# ProDoc_ChisFlash-MBC5-v1_21_8M.net
KiCad netlist of a schematic drawn in EasyEDA Pro
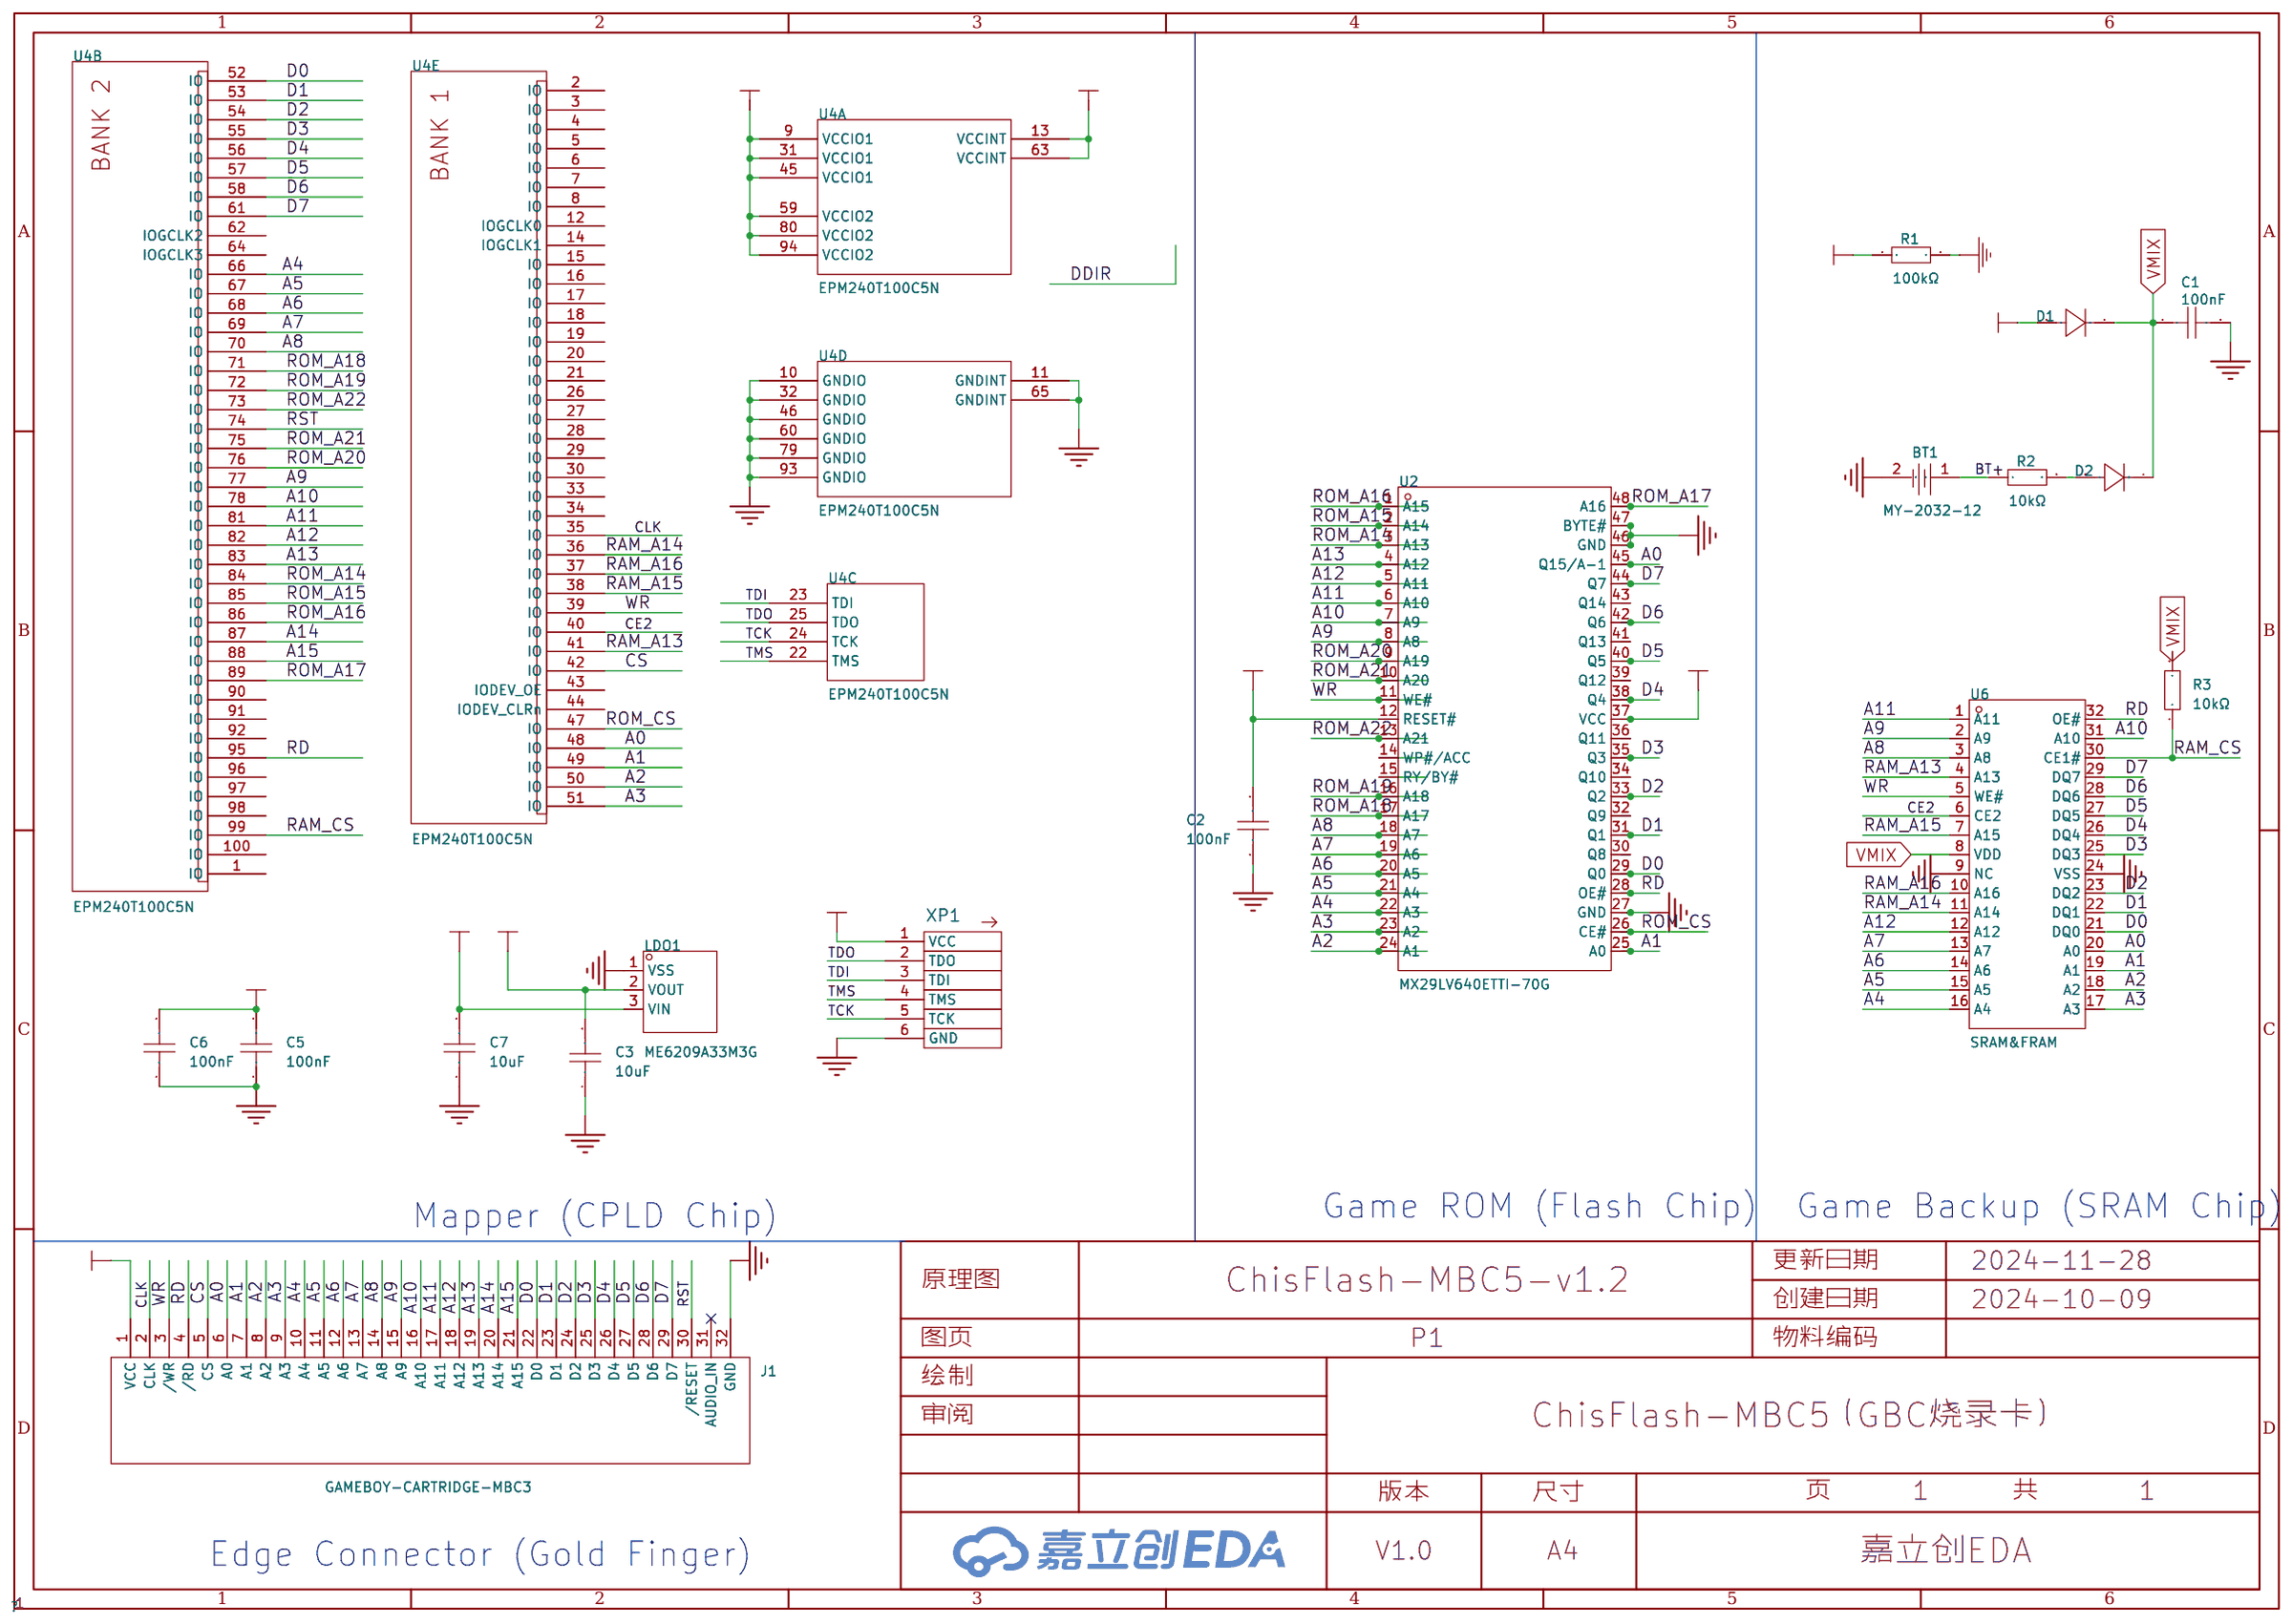
[diagram p0: schematic sheet]

(export (version "E")
  (design (tool "Eeschema 10.0.6"))
  (components
    (comp (ref "BT1")
      (value "MY-2032-12")
      (footprint "easyedapro:BAT-SMD_MY-2032-12")
      (fields (field (name "Manufacturer") "MYOUNG(美阳)"))
      (libsource (lib "easyedapro") (part "MY-2032-12"))
    )
    (comp (ref "C1")
      (value "100nF")
      (footprint "easyedapro:C0603")
      (description "容值:100nF;精度:±10%;额定电压:50V;材质(温度系数):X7R;")
      (fields
        (field (name "Manufacturer Part") "CGA0603X7R104K500JT")
        (field (name "Manufacturer") "HRE(芯声)")
      )
      (libsource (lib "easyedapro") (part "CGA0603X7R104K500JT"))
    )
    (comp (ref "C2")
      (value "100nF")
      (footprint "easyedapro:C0603")
      (description "容值:100nF;精度:±10%;额定电压:50V;材质(温度系数):X7R;")
      (fields
        (field (name "Manufacturer Part") "CGA0603X7R104K500JT")
        (field (name "Manufacturer") "HRE(芯声)")
      )
      (libsource (lib "easyedapro") (part "CGA0603X7R104K500JT"))
    )
    (comp (ref "C3")
      (value "10uF")
      (footprint "easyedapro:C0603")
      (description "容值:10uF;精度:±20%;额定电压:25V;材质(温度系数):X5R;")
      (fields
        (field (name "Manufacturer Part") "CL10A106MA8NRNC")
        (field (name "Manufacturer") "SAMSUNG(三星)")
      )
      (libsource (lib "easyedapro") (part "CL10A106MA8NRNC"))
    )
    (comp (ref "C5")
      (value "100nF")
      (footprint "easyedapro:C0603")
      (description "容值:100nF;精度:±10%;额定电压:50V;材质(温度系数):X7R;")
      (fields
        (field (name "Manufacturer Part") "CGA0603X7R104K500JT")
        (field (name "Manufacturer") "HRE(芯声)")
      )
      (libsource (lib "easyedapro") (part "CGA0603X7R104K500JT"))
    )
    (comp (ref "C6")
      (value "100nF")
      (footprint "easyedapro:C0603")
      (description "容值:100nF;精度:±10%;额定电压:50V;材质(温度系数):X7R;")
      (fields
        (field (name "Manufacturer Part") "CGA0603X7R104K500JT")
        (field (name "Manufacturer") "HRE(芯声)")
      )
      (libsource (lib "easyedapro") (part "CGA0603X7R104K500JT"))
    )
    (comp (ref "C7")
      (value "10uF")
      (footprint "easyedapro:C0603")
      (description "容值:10uF;精度:±20%;额定电压:25V;材质(温度系数):X5R;")
      (fields
        (field (name "Manufacturer Part") "CL10A106MA8NRNC")
        (field (name "Manufacturer") "SAMSUNG(三星)")
      )
      (libsource (lib "easyedapro") (part "CL10A106MA8NRNC"))
    )
    (comp (ref "D1")
      (value "1N4148WS")
      (footprint "easyedapro:SOD-323_L1.8-W1.3-LS2.5-RD")
      (description "二极管配置:独立式;正向压降(Vf):1.25V@150mA;直流反向耐压(Vr):100V;平均整流电流(Io):300mA;功率:400mW;反向恢复时间(trr):8ns;")
      (fields (field (name "Manufacturer") "JSMSEMI(杰盛微)"))
      (libsource (lib "easyedapro") (part "1N4148WS_C917117"))
    )
    (comp (ref "D2")
      (value "1N4148WS")
      (footprint "easyedapro:SOD-323_L1.8-W1.3-LS2.5-RD")
      (description "二极管配置:独立式;正向压降(Vf):1.25V@150mA;直流反向耐压(Vr):100V;平均整流电流(Io):300mA;功率:400mW;反向恢复时间(trr):8ns;")
      (fields (field (name "Manufacturer") "JSMSEMI(杰盛微)"))
      (libsource (lib "easyedapro") (part "1N4148WS_C917117"))
    )
    (comp (ref "J1")
      (value "GAMEBOY-CARTRIDGE-MBC3")
      (footprint "easyedapro:GAMEBOY_CARTRIDGE_PIN")
      (libsource (lib "easyedapro") (part "GAMEBOY-CARTRIDGE-MBC3"))
    )
    (comp (ref "LDO1")
      (value "ME6209A33M3G")
      (footprint "easyedapro:SOT-23-3_L2.9-W1.6-P1.90-LS2.8-BR")
      (description "输出类型:固定;最大输入电压:18V;输出电压:3.3V;最大输出电流:250mA;电源纹波抑制比(PSRR):-;输出极性:正极;")
      (fields (field (name "Manufacturer") "MICRONE(南京微盟)"))
      (libsource (lib "easyedapro") (part "ME6209A33M3G"))
    )
    (comp (ref "R1")
      (value "100kΩ")
      (footprint "easyedapro:R0603")
      (description "电阻类型:厚膜电阻;阻值:100kΩ;精度:±1%;功率:100mW;最大工作电压:75V;温度系数:±100ppm/°C;")
      (fields
        (field (name "Manufacturer Part") "0603WAF1003T5E")
        (field (name "Manufacturer") "UNI-ROYAL(厚声)")
      )
      (libsource (lib "easyedapro") (part "0603WAF1003T5E"))
    )
    (comp (ref "R2")
      (value "10kΩ")
      (footprint "easyedapro:R0603")
      (description "电阻类型:厚膜电阻;阻值:10kΩ;精度:±1%;功率:100mW;温度系数:±100ppm/°C;最大工作电压:75V;工作温度范围:-55°C~+155°C;")
      (fields
        (field (name "Manufacturer Part") "0603WAF1002T5E")
        (field (name "Manufacturer") "UNI-ROYAL(厚声)")
      )
      (libsource (lib "easyedapro") (part "0603WAF1002T5E"))
    )
    (comp (ref "R3")
      (value "10kΩ")
      (footprint "easyedapro:R0603")
      (description "电阻类型:厚膜电阻;阻值:10kΩ;精度:±1%;功率:100mW;温度系数:±100ppm/°C;最大工作电压:75V;工作温度范围:-55°C~+155°C;")
      (fields
        (field (name "Manufacturer Part") "0603WAF1002T5E")
        (field (name "Manufacturer") "UNI-ROYAL(厚声)")
      )
      (libsource (lib "easyedapro") (part "0603WAF1002T5E"))
    )
    (comp (ref "U2")
      (value "MX29LV640ETTI-70G")
      (footprint "easyedapro:TSOP-48_L12.0-W18.4-P0.50-LS20.0-BL")
      (fields (field (name "Manufacturer") "MXIC(旺宏电子)"))
      (libsource (lib "easyedapro") (part "MX29LV640ETTI-70G"))
    )
    (comp (ref "U4")
      (value "EPM240T100C5N")
      (footprint "easyedapro:TQFP-100_L14.0-W14.0-P0.50-LS16.0-BL")
      (description "类型:其它PLD;逻辑门数量:-;逻辑单元数:-;逻辑阵列块数:240;")
      (fields (field (name "Manufacturer") "Intel/Altera"))
      (libsource (lib "easyedapro") (part "EPM240T100C5N"))
    )
    (comp (ref "U6")
      (value "SRAM&FRAM")
      (footprint "easyedapro:TSSOP-TSOP二合一")
      (libsource (lib "easyedapro") (part "SRAM&FRAM"))
    )
    (comp (ref "XP1")
      (value "JTAG")
      (footprint "easyedapro:HDR-TH_6P-P1.27-V-M-1")
      (libsource (lib "easyedapro") (part "jtag"))
    )
  )
  (nets
    (net (code "1") (name "+3V3") (class "Default")
      (node (ref "C2") (pin "2") (pinfunction "2_2") (pintype "unspecified"))
      (node (ref "C3") (pin "2") (pinfunction "2_2") (pintype "unspecified"))
      (node (ref "C5") (pin "2") (pinfunction "2_2") (pintype "unspecified"))
      (node (ref "C6") (pin "2") (pinfunction "2_2") (pintype "unspecified"))
      (node (ref "D1") (pin "2") (pinfunction "A_2") (pintype "unspecified"))
      (node (ref "LDO1") (pin "2") (pinfunction "VOUT_2") (pintype "unspecified"))
      (node (ref "R1") (pin "1") (pinfunction "1_1") (pintype "input"))
      (node (ref "U2") (pin "12") (pinfunction "RESET#_12") (pintype "unspecified"))
      (node (ref "U2") (pin "37") (pinfunction "VCC_37") (pintype "unspecified"))
      (node (ref "U4") (pin "13") (pinfunction "VCCINT_13") (pintype "unspecified"))
      (node (ref "U4") (pin "31") (pinfunction "VCCIO1_31") (pintype "unspecified"))
      (node (ref "U4") (pin "45") (pinfunction "VCCIO1_45") (pintype "unspecified"))
      (node (ref "U4") (pin "59") (pinfunction "VCCIO2_59") (pintype "unspecified"))
      (node (ref "U4") (pin "63") (pinfunction "VCCINT_63") (pintype "unspecified"))
      (node (ref "U4") (pin "80") (pinfunction "VCCIO2_80") (pintype "unspecified"))
      (node (ref "U4") (pin "9") (pinfunction "VCCIO1_9") (pintype "unspecified"))
      (node (ref "U4") (pin "94") (pinfunction "VCCIO2_94") (pintype "unspecified"))
      (node (ref "XP1") (pin "1") (pinfunction "VCC_1") (pintype "output"))
    )
    (net (code "2") (name "+5V") (class "Default")
      (node (ref "C7") (pin "2") (pinfunction "2_2") (pintype "unspecified"))
      (node (ref "J1") (pin "1") (pinfunction "VCC_1") (pintype "unspecified"))
      (node (ref "LDO1") (pin "3") (pinfunction "VIN_3") (pintype "unspecified"))
    )
    (net (code "3") (name "/A0") (class "Default")
      (node (ref "J1") (pin "6") (pinfunction "A0_6") (pintype "unspecified"))
      (node (ref "U2") (pin "45") (pinfunction "Q15/A-1_45") (pintype "unspecified"))
      (node (ref "U4") (pin "48") (pinfunction "IO_48") (pintype "bidirectional"))
      (node (ref "U6") (pin "20") (pinfunction "A0_20") (pintype "unspecified"))
    )
    (net (code "4") (name "/A1") (class "Default")
      (node (ref "J1") (pin "7") (pinfunction "A1_7") (pintype "unspecified"))
      (node (ref "U2") (pin "25") (pinfunction "A0_25") (pintype "unspecified"))
      (node (ref "U4") (pin "49") (pinfunction "IO_49") (pintype "bidirectional"))
      (node (ref "U6") (pin "19") (pinfunction "A1_19") (pintype "unspecified"))
    )
    (net (code "5") (name "/A2") (class "Default")
      (node (ref "J1") (pin "8") (pinfunction "A2_8") (pintype "unspecified"))
      (node (ref "U2") (pin "24") (pinfunction "A1_24") (pintype "unspecified"))
      (node (ref "U4") (pin "50") (pinfunction "IO_50") (pintype "bidirectional"))
      (node (ref "U6") (pin "18") (pinfunction "A2_18") (pintype "unspecified"))
    )
    (net (code "6") (name "/A3") (class "Default")
      (node (ref "J1") (pin "9") (pinfunction "A3_9") (pintype "unspecified"))
      (node (ref "U2") (pin "23") (pinfunction "A2_23") (pintype "unspecified"))
      (node (ref "U4") (pin "51") (pinfunction "IO_51") (pintype "bidirectional"))
      (node (ref "U6") (pin "17") (pinfunction "A3_17") (pintype "unspecified"))
    )
    (net (code "7") (name "/A4") (class "Default")
      (node (ref "J1") (pin "10") (pinfunction "A4_10") (pintype "unspecified"))
      (node (ref "U2") (pin "22") (pinfunction "A3_22") (pintype "unspecified"))
      (node (ref "U4") (pin "66") (pinfunction "IO_66") (pintype "bidirectional"))
      (node (ref "U6") (pin "16") (pinfunction "A4_16") (pintype "unspecified"))
    )
    (net (code "8") (name "/A5") (class "Default")
      (node (ref "J1") (pin "11") (pinfunction "A5_11") (pintype "unspecified"))
      (node (ref "U2") (pin "21") (pinfunction "A4_21") (pintype "unspecified"))
      (node (ref "U4") (pin "67") (pinfunction "IO_67") (pintype "bidirectional"))
      (node (ref "U6") (pin "15") (pinfunction "A5_15") (pintype "unspecified"))
    )
    (net (code "9") (name "/A6") (class "Default")
      (node (ref "J1") (pin "12") (pinfunction "A6_12") (pintype "unspecified"))
      (node (ref "U2") (pin "20") (pinfunction "A5_20") (pintype "unspecified"))
      (node (ref "U4") (pin "68") (pinfunction "IO_68") (pintype "bidirectional"))
      (node (ref "U6") (pin "14") (pinfunction "A6_14") (pintype "unspecified"))
    )
    (net (code "10") (name "/A7") (class "Default")
      (node (ref "J1") (pin "13") (pinfunction "A7_13") (pintype "unspecified"))
      (node (ref "U2") (pin "19") (pinfunction "A6_19") (pintype "unspecified"))
      (node (ref "U4") (pin "69") (pinfunction "IO_69") (pintype "bidirectional"))
      (node (ref "U6") (pin "13") (pinfunction "A7_13") (pintype "unspecified"))
    )
    (net (code "11") (name "/A8") (class "Default")
      (node (ref "J1") (pin "14") (pinfunction "A8_14") (pintype "unspecified"))
      (node (ref "U2") (pin "18") (pinfunction "A7_18") (pintype "unspecified"))
      (node (ref "U4") (pin "70") (pinfunction "IO_70") (pintype "bidirectional"))
      (node (ref "U6") (pin "3") (pinfunction "A8_3") (pintype "unspecified"))
    )
    (net (code "12") (name "/A9") (class "Default")
      (node (ref "J1") (pin "15") (pinfunction "A9_15") (pintype "unspecified"))
      (node (ref "U2") (pin "8") (pinfunction "A8_8") (pintype "unspecified"))
      (node (ref "U4") (pin "77") (pinfunction "IO_77") (pintype "bidirectional"))
      (node (ref "U6") (pin "2") (pinfunction "A9_2") (pintype "unspecified"))
    )
    (net (code "13") (name "/A10") (class "Default")
      (node (ref "J1") (pin "16") (pinfunction "A10_16") (pintype "unspecified"))
      (node (ref "U2") (pin "7") (pinfunction "A9_7") (pintype "unspecified"))
      (node (ref "U4") (pin "78") (pinfunction "IO_78") (pintype "bidirectional"))
      (node (ref "U6") (pin "31") (pinfunction "A10_31") (pintype "unspecified"))
    )
    (net (code "14") (name "/A11") (class "Default")
      (node (ref "J1") (pin "17") (pinfunction "A11_17") (pintype "unspecified"))
      (node (ref "U2") (pin "6") (pinfunction "A10_6") (pintype "unspecified"))
      (node (ref "U4") (pin "81") (pinfunction "IO_81") (pintype "bidirectional"))
      (node (ref "U6") (pin "1") (pinfunction "A11_1") (pintype "unspecified"))
    )
    (net (code "15") (name "/A12") (class "Default")
      (node (ref "J1") (pin "18") (pinfunction "A12_18") (pintype "unspecified"))
      (node (ref "U2") (pin "5") (pinfunction "A11_5") (pintype "unspecified"))
      (node (ref "U4") (pin "82") (pinfunction "IO_82") (pintype "bidirectional"))
      (node (ref "U6") (pin "12") (pinfunction "A12_12") (pintype "unspecified"))
    )
    (net (code "16") (name "/A13") (class "Default")
      (node (ref "J1") (pin "19") (pinfunction "A13_19") (pintype "unspecified"))
      (node (ref "U2") (pin "4") (pinfunction "A12_4") (pintype "unspecified"))
      (node (ref "U4") (pin "83") (pinfunction "IO_83") (pintype "bidirectional"))
    )
    (net (code "17") (name "/A14") (class "Default")
      (node (ref "J1") (pin "20") (pinfunction "A14_20") (pintype "unspecified"))
      (node (ref "U4") (pin "87") (pinfunction "IO_87") (pintype "bidirectional"))
    )
    (net (code "18") (name "/A15") (class "Default")
      (node (ref "J1") (pin "21") (pinfunction "A15_21") (pintype "unspecified"))
      (node (ref "U4") (pin "88") (pinfunction "IO_88") (pintype "bidirectional"))
    )
    (net (code "19") (name "/BT+") (class "Default")
      (node (ref "BT1") (pin "1") (pinfunction "1_1") (pintype "input"))
      (node (ref "R2") (pin "1") (pinfunction "1_1") (pintype "input"))
    )
    (net (code "20") (name "/CE2") (class "Default")
      (node (ref "U4") (pin "40") (pinfunction "IO_40") (pintype "bidirectional"))
      (node (ref "U6") (pin "6") (pinfunction "CE2_6") (pintype "unspecified"))
    )
    (net (code "21") (name "/CLK") (class "Default")
      (node (ref "J1") (pin "2") (pinfunction "CLK_2") (pintype "unspecified"))
      (node (ref "U4") (pin "35") (pinfunction "IO_35") (pintype "bidirectional"))
    )
    (net (code "22") (name "/CS") (class "Default")
      (node (ref "J1") (pin "5") (pinfunction "CS_5") (pintype "unspecified"))
      (node (ref "U4") (pin "42") (pinfunction "IO_42") (pintype "bidirectional"))
    )
    (net (code "23") (name "/D0") (class "Default")
      (node (ref "J1") (pin "22") (pinfunction "D0_22") (pintype "unspecified"))
      (node (ref "U2") (pin "29") (pinfunction "Q0_29") (pintype "unspecified"))
      (node (ref "U4") (pin "52") (pinfunction "IO_52") (pintype "bidirectional"))
      (node (ref "U6") (pin "21") (pinfunction "DQ0_21") (pintype "unspecified"))
    )
    (net (code "24") (name "/D1") (class "Default")
      (node (ref "J1") (pin "23") (pinfunction "D1_23") (pintype "unspecified"))
      (node (ref "U2") (pin "31") (pinfunction "Q1_31") (pintype "unspecified"))
      (node (ref "U4") (pin "53") (pinfunction "IO_53") (pintype "bidirectional"))
      (node (ref "U6") (pin "22") (pinfunction "DQ1_22") (pintype "unspecified"))
    )
    (net (code "25") (name "/D2") (class "Default")
      (node (ref "J1") (pin "24") (pinfunction "D2_24") (pintype "unspecified"))
      (node (ref "U2") (pin "33") (pinfunction "Q2_33") (pintype "unspecified"))
      (node (ref "U4") (pin "54") (pinfunction "IO_54") (pintype "bidirectional"))
      (node (ref "U6") (pin "23") (pinfunction "DQ2_23") (pintype "unspecified"))
    )
    (net (code "26") (name "/D3") (class "Default")
      (node (ref "J1") (pin "25") (pinfunction "D3_25") (pintype "unspecified"))
      (node (ref "U2") (pin "35") (pinfunction "Q3_35") (pintype "unspecified"))
      (node (ref "U4") (pin "55") (pinfunction "IO_55") (pintype "bidirectional"))
      (node (ref "U6") (pin "25") (pinfunction "DQ3_25") (pintype "unspecified"))
    )
    (net (code "27") (name "/D4") (class "Default")
      (node (ref "J1") (pin "26") (pinfunction "D4_26") (pintype "unspecified"))
      (node (ref "U2") (pin "38") (pinfunction "Q4_38") (pintype "unspecified"))
      (node (ref "U4") (pin "56") (pinfunction "IO_56") (pintype "bidirectional"))
      (node (ref "U6") (pin "26") (pinfunction "DQ4_26") (pintype "unspecified"))
    )
    (net (code "28") (name "/D5") (class "Default")
      (node (ref "J1") (pin "27") (pinfunction "D5_27") (pintype "unspecified"))
      (node (ref "U2") (pin "40") (pinfunction "Q5_40") (pintype "unspecified"))
      (node (ref "U4") (pin "57") (pinfunction "IO_57") (pintype "bidirectional"))
      (node (ref "U6") (pin "27") (pinfunction "DQ5_27") (pintype "unspecified"))
    )
    (net (code "29") (name "/D6") (class "Default")
      (node (ref "J1") (pin "28") (pinfunction "D6_28") (pintype "unspecified"))
      (node (ref "U2") (pin "42") (pinfunction "Q6_42") (pintype "unspecified"))
      (node (ref "U4") (pin "58") (pinfunction "IO_58") (pintype "bidirectional"))
      (node (ref "U6") (pin "28") (pinfunction "DQ6_28") (pintype "unspecified"))
    )
    (net (code "30") (name "/D7") (class "Default")
      (node (ref "J1") (pin "29") (pinfunction "D7_29") (pintype "unspecified"))
      (node (ref "U2") (pin "44") (pinfunction "Q7_44") (pintype "unspecified"))
      (node (ref "U4") (pin "61") (pinfunction "IO_61") (pintype "bidirectional"))
      (node (ref "U6") (pin "29") (pinfunction "DQ7_29") (pintype "unspecified"))
    )
    (net (code "32") (name "/RAM_A13") (class "Default")
      (node (ref "U4") (pin "41") (pinfunction "IO_41") (pintype "bidirectional"))
      (node (ref "U6") (pin "4") (pinfunction "A13_4") (pintype "unspecified"))
    )
    (net (code "33") (name "/RAM_A14") (class "Default")
      (node (ref "U4") (pin "36") (pinfunction "IO_36") (pintype "bidirectional"))
      (node (ref "U6") (pin "11") (pinfunction "A14_11") (pintype "unspecified"))
    )
    (net (code "34") (name "/RAM_A15") (class "Default")
      (node (ref "U4") (pin "38") (pinfunction "IO_38") (pintype "bidirectional"))
      (node (ref "U6") (pin "7") (pinfunction "A15_7") (pintype "unspecified"))
    )
    (net (code "35") (name "/RAM_A16") (class "Default")
      (node (ref "U4") (pin "37") (pinfunction "IO_37") (pintype "bidirectional"))
      (node (ref "U6") (pin "10") (pinfunction "A16_10") (pintype "unspecified"))
    )
    (net (code "36") (name "/RAM_CS") (class "Default")
      (node (ref "R3") (pin "1") (pinfunction "1_1") (pintype "input"))
      (node (ref "U4") (pin "99") (pinfunction "IO_99") (pintype "bidirectional"))
      (node (ref "U6") (pin "30") (pinfunction "CE1#_30") (pintype "unspecified"))
    )
    (net (code "37") (name "/RD") (class "Default")
      (node (ref "J1") (pin "4") (pinfunction "/RD_4") (pintype "unspecified"))
      (node (ref "U2") (pin "28") (pinfunction "OE#_28") (pintype "unspecified"))
      (node (ref "U4") (pin "95") (pinfunction "IO_95") (pintype "bidirectional"))
      (node (ref "U6") (pin "32") (pinfunction "OE#_32") (pintype "unspecified"))
    )
    (net (code "38") (name "/ROM_A14") (class "Default")
      (node (ref "U2") (pin "3") (pinfunction "A13_3") (pintype "unspecified"))
      (node (ref "U4") (pin "84") (pinfunction "IO_84") (pintype "bidirectional"))
    )
    (net (code "39") (name "/ROM_A15") (class "Default")
      (node (ref "U2") (pin "2") (pinfunction "A14_2") (pintype "unspecified"))
      (node (ref "U4") (pin "85") (pinfunction "IO_85") (pintype "bidirectional"))
    )
    (net (code "40") (name "/ROM_A16") (class "Default")
      (node (ref "U2") (pin "1") (pinfunction "A15_1") (pintype "unspecified"))
      (node (ref "U4") (pin "86") (pinfunction "IO_86") (pintype "bidirectional"))
    )
    (net (code "41") (name "/ROM_A17") (class "Default")
      (node (ref "U2") (pin "48") (pinfunction "A16_48") (pintype "unspecified"))
      (node (ref "U4") (pin "89") (pinfunction "IO_89") (pintype "bidirectional"))
    )
    (net (code "42") (name "/ROM_A18") (class "Default")
      (node (ref "U2") (pin "17") (pinfunction "A17_17") (pintype "unspecified"))
      (node (ref "U4") (pin "71") (pinfunction "IO_71") (pintype "bidirectional"))
    )
    (net (code "43") (name "/ROM_A19") (class "Default")
      (node (ref "U2") (pin "16") (pinfunction "A18_16") (pintype "unspecified"))
      (node (ref "U4") (pin "72") (pinfunction "IO_72") (pintype "bidirectional"))
    )
    (net (code "44") (name "/ROM_A20") (class "Default")
      (node (ref "U2") (pin "9") (pinfunction "A19_9") (pintype "unspecified"))
      (node (ref "U4") (pin "76") (pinfunction "IO_76") (pintype "bidirectional"))
    )
    (net (code "45") (name "/ROM_A21") (class "Default")
      (node (ref "U2") (pin "10") (pinfunction "A20_10") (pintype "unspecified"))
      (node (ref "U4") (pin "75") (pinfunction "IO_75") (pintype "bidirectional"))
    )
    (net (code "46") (name "/ROM_A22") (class "Default")
      (node (ref "U2") (pin "13") (pinfunction "A21_13") (pintype "unspecified"))
      (node (ref "U4") (pin "73") (pinfunction "IO_73") (pintype "bidirectional"))
    )
    (net (code "47") (name "/ROM_CS") (class "Default")
      (node (ref "U2") (pin "26") (pinfunction "CE#_26") (pintype "unspecified"))
      (node (ref "U4") (pin "47") (pinfunction "IO_47") (pintype "bidirectional"))
    )
    (net (code "48") (name "/RST") (class "Default")
      (node (ref "J1") (pin "30") (pinfunction "/RESET_30") (pintype "unspecified"))
      (node (ref "U4") (pin "74") (pinfunction "IO_74") (pintype "bidirectional"))
    )
    (net (code "49") (name "/TCK") (class "Default")
      (node (ref "U4") (pin "24") (pinfunction "TCK_24") (pintype "unspecified"))
      (node (ref "XP1") (pin "5") (pinfunction "TCK_5") (pintype "input"))
    )
    (net (code "50") (name "/TDI") (class "Default")
      (node (ref "U4") (pin "23") (pinfunction "TDI_23") (pintype "unspecified"))
      (node (ref "XP1") (pin "3") (pinfunction "TDI_3") (pintype "output"))
    )
    (net (code "51") (name "/TDO") (class "Default")
      (node (ref "U4") (pin "25") (pinfunction "TDO_25") (pintype "output"))
      (node (ref "XP1") (pin "2") (pinfunction "TDO_2") (pintype "output"))
    )
    (net (code "52") (name "/TMS") (class "Default")
      (node (ref "U4") (pin "22") (pinfunction "TMS_22") (pintype "unspecified"))
      (node (ref "XP1") (pin "4") (pinfunction "TMS_4") (pintype "output"))
    )
    (net (code "53") (name "/WR") (class "Default")
      (node (ref "J1") (pin "3") (pinfunction "/WR_3") (pintype "unspecified"))
      (node (ref "U2") (pin "11") (pinfunction "WE#_11") (pintype "unspecified"))
      (node (ref "U4") (pin "39") (pinfunction "IO_39") (pintype "bidirectional"))
      (node (ref "U6") (pin "5") (pinfunction "WE#_5") (pintype "unspecified"))
    )
    (net (code "54") (name "GND") (class "Default")
      (node (ref "BT1") (pin "2") (pinfunction "2_2") (pintype "input"))
      (node (ref "C1") (pin "2") (pinfunction "2_2") (pintype "unspecified"))
      (node (ref "C2") (pin "1") (pinfunction "1_1") (pintype "unspecified"))
      (node (ref "C3") (pin "1") (pinfunction "1_1") (pintype "unspecified"))
      (node (ref "C5") (pin "1") (pinfunction "1_1") (pintype "unspecified"))
      (node (ref "C6") (pin "1") (pinfunction "1_1") (pintype "unspecified"))
      (node (ref "C7") (pin "1") (pinfunction "1_1") (pintype "unspecified"))
      (node (ref "J1") (pin "32") (pinfunction "GND_32") (pintype "unspecified"))
      (node (ref "LDO1") (pin "1") (pinfunction "VSS_1") (pintype "unspecified"))
      (node (ref "R1") (pin "2") (pinfunction "2_2") (pintype "input"))
      (node (ref "U2") (pin "27") (pinfunction "GND_27") (pintype "unspecified"))
      (node (ref "U2") (pin "46") (pinfunction "GND_46") (pintype "unspecified"))
      (node (ref "U2") (pin "47") (pinfunction "BYTE#_47") (pintype "unspecified"))
      (node (ref "U4") (pin "10") (pinfunction "GNDIO_10") (pintype "unspecified"))
      (node (ref "U4") (pin "11") (pinfunction "GNDINT_11") (pintype "unspecified"))
      (node (ref "U4") (pin "32") (pinfunction "GNDIO_32") (pintype "unspecified"))
      (node (ref "U4") (pin "46") (pinfunction "GNDIO_46") (pintype "unspecified"))
      (node (ref "U4") (pin "60") (pinfunction "GNDIO_60") (pintype "unspecified"))
      (node (ref "U4") (pin "65") (pinfunction "GNDINT_65") (pintype "unspecified"))
      (node (ref "U4") (pin "79") (pinfunction "GNDIO_79") (pintype "unspecified"))
      (node (ref "U4") (pin "93") (pinfunction "GNDIO_93") (pintype "unspecified"))
      (node (ref "U6") (pin "24") (pinfunction "VSS_24") (pintype "unspecified"))
      (node (ref "U6") (pin "9") (pinfunction "NC_9") (pintype "unspecified"))
      (node (ref "XP1") (pin "6") (pinfunction "GND_6") (pintype "input"))
    )
    (net (code "55") (name "Net-(D2-A)") (class "Default")
      (node (ref "D2") (pin "2") (pinfunction "A_2") (pintype "unspecified"))
      (node (ref "R2") (pin "2") (pinfunction "2_2") (pintype "input"))
    )
    (net (code "56") (name "VMIX") (class "Default")
      (node (ref "C1") (pin "1") (pinfunction "1_1") (pintype "unspecified"))
      (node (ref "D1") (pin "1") (pinfunction "C_1") (pintype "unspecified"))
      (node (ref "D2") (pin "1") (pinfunction "C_1") (pintype "unspecified"))
      (node (ref "R3") (pin "2") (pinfunction "2_2") (pintype "input"))
      (node (ref "U6") (pin "8") (pinfunction "VDD_8") (pintype "unspecified"))
    )
    (net (code "57") (name "unconnected-(J1-AUDIO_IN-Pad31)") (class "Default")
      (node (ref "J1") (pin "31") (pinfunction "AUDIO_IN_31") (pintype "unspecified+no_connect"))
    )
    (net (code "58") (name "unconnected-(U2-Q8-Pad30)") (class "Default")
      (node (ref "U2") (pin "30") (pinfunction "Q8_30") (pintype "unspecified"))
    )
    (net (code "59") (name "unconnected-(U2-Q9-Pad32)") (class "Default")
      (node (ref "U2") (pin "32") (pinfunction "Q9_32") (pintype "unspecified"))
    )
    (net (code "60") (name "unconnected-(U2-Q10-Pad34)") (class "Default")
      (node (ref "U2") (pin "34") (pinfunction "Q10_34") (pintype "unspecified"))
    )
    (net (code "61") (name "unconnected-(U2-Q11-Pad36)") (class "Default")
      (node (ref "U2") (pin "36") (pinfunction "Q11_36") (pintype "unspecified"))
    )
    (net (code "62") (name "unconnected-(U2-Q12-Pad39)") (class "Default")
      (node (ref "U2") (pin "39") (pinfunction "Q12_39") (pintype "unspecified"))
    )
    (net (code "63") (name "unconnected-(U2-Q13-Pad41)") (class "Default")
      (node (ref "U2") (pin "41") (pinfunction "Q13_41") (pintype "unspecified"))
    )
    (net (code "64") (name "unconnected-(U2-Q14-Pad43)") (class "Default")
      (node (ref "U2") (pin "43") (pinfunction "Q14_43") (pintype "unspecified"))
    )
    (net (code "65") (name "unconnected-(U2-RY{slash}BY#-Pad15)") (class "Default")
      (node (ref "U2") (pin "15") (pinfunction "RY/BY#_15") (pintype "unspecified"))
    )
    (net (code "66") (name "unconnected-(U2-WP#{slash}ACC-Pad14)") (class "Default")
      (node (ref "U2") (pin "14") (pinfunction "WP#/ACC_14") (pintype "unspecified"))
    )
    (net (code "67") (name "unconnected-(U4B-IO-Pad1)") (class "Default")
      (node (ref "U4") (pin "1") (pinfunction "IO_1") (pintype "bidirectional"))
    )
    (net (code "68") (name "unconnected-(U4B-IO-Pad90)") (class "Default")
      (node (ref "U4") (pin "90") (pinfunction "IO_90") (pintype "bidirectional"))
    )
    (net (code "69") (name "unconnected-(U4B-IO-Pad91)") (class "Default")
      (node (ref "U4") (pin "91") (pinfunction "IO_91") (pintype "bidirectional"))
    )
    (net (code "70") (name "unconnected-(U4B-IO-Pad92)") (class "Default")
      (node (ref "U4") (pin "92") (pinfunction "IO_92") (pintype "bidirectional"))
    )
    (net (code "71") (name "unconnected-(U4B-IO-Pad96)") (class "Default")
      (node (ref "U4") (pin "96") (pinfunction "IO_96") (pintype "bidirectional"))
    )
    (net (code "72") (name "unconnected-(U4B-IO-Pad97)") (class "Default")
      (node (ref "U4") (pin "97") (pinfunction "IO_97") (pintype "bidirectional"))
    )
    (net (code "73") (name "unconnected-(U4B-IO-Pad98)") (class "Default")
      (node (ref "U4") (pin "98") (pinfunction "IO_98") (pintype "bidirectional"))
    )
    (net (code "74") (name "unconnected-(U4B-IO-Pad100)") (class "Default")
      (node (ref "U4") (pin "100") (pinfunction "IO_100") (pintype "bidirectional"))
    )
    (net (code "75") (name "unconnected-(U4B-IOGCLK2-Pad62)") (class "Default")
      (node (ref "U4") (pin "62") (pinfunction "IOGCLK2_62") (pintype "bidirectional"))
    )
    (net (code "76") (name "unconnected-(U4B-IOGCLK3-Pad64)") (class "Default")
      (node (ref "U4") (pin "64") (pinfunction "IOGCLK3_64") (pintype "bidirectional"))
    )
    (net (code "77") (name "unconnected-(U4E-IO-Pad2)") (class "Default")
      (node (ref "U4") (pin "2") (pinfunction "IO_2") (pintype "bidirectional"))
    )
    (net (code "78") (name "unconnected-(U4E-IO-Pad3)") (class "Default")
      (node (ref "U4") (pin "3") (pinfunction "IO_3") (pintype "bidirectional"))
    )
    (net (code "79") (name "unconnected-(U4E-IO-Pad4)") (class "Default")
      (node (ref "U4") (pin "4") (pinfunction "IO_4") (pintype "bidirectional"))
    )
    (net (code "80") (name "unconnected-(U4E-IO-Pad5)") (class "Default")
      (node (ref "U4") (pin "5") (pinfunction "IO_5") (pintype "bidirectional"))
    )
    (net (code "81") (name "unconnected-(U4E-IO-Pad6)") (class "Default")
      (node (ref "U4") (pin "6") (pinfunction "IO_6") (pintype "bidirectional"))
    )
    (net (code "82") (name "unconnected-(U4E-IO-Pad7)") (class "Default")
      (node (ref "U4") (pin "7") (pinfunction "IO_7") (pintype "bidirectional"))
    )
    (net (code "83") (name "unconnected-(U4E-IO-Pad8)") (class "Default")
      (node (ref "U4") (pin "8") (pinfunction "IO_8") (pintype "bidirectional"))
    )
    (net (code "84") (name "unconnected-(U4E-IO-Pad15)") (class "Default")
      (node (ref "U4") (pin "15") (pinfunction "IO_15") (pintype "bidirectional"))
    )
    (net (code "85") (name "unconnected-(U4E-IO-Pad16)") (class "Default")
      (node (ref "U4") (pin "16") (pinfunction "IO_16") (pintype "bidirectional"))
    )
    (net (code "86") (name "unconnected-(U4E-IO-Pad17)") (class "Default")
      (node (ref "U4") (pin "17") (pinfunction "IO_17") (pintype "bidirectional"))
    )
    (net (code "87") (name "unconnected-(U4E-IO-Pad18)") (class "Default")
      (node (ref "U4") (pin "18") (pinfunction "IO_18") (pintype "bidirectional"))
    )
    (net (code "88") (name "unconnected-(U4E-IO-Pad19)") (class "Default")
      (node (ref "U4") (pin "19") (pinfunction "IO_19") (pintype "bidirectional"))
    )
    (net (code "89") (name "unconnected-(U4E-IO-Pad20)") (class "Default")
      (node (ref "U4") (pin "20") (pinfunction "IO_20") (pintype "bidirectional"))
    )
    (net (code "90") (name "unconnected-(U4E-IO-Pad21)") (class "Default")
      (node (ref "U4") (pin "21") (pinfunction "IO_21") (pintype "bidirectional"))
    )
    (net (code "91") (name "unconnected-(U4E-IO-Pad26)") (class "Default")
      (node (ref "U4") (pin "26") (pinfunction "IO_26") (pintype "bidirectional"))
    )
    (net (code "92") (name "unconnected-(U4E-IO-Pad27)") (class "Default")
      (node (ref "U4") (pin "27") (pinfunction "IO_27") (pintype "bidirectional"))
    )
    (net (code "93") (name "unconnected-(U4E-IO-Pad28)") (class "Default")
      (node (ref "U4") (pin "28") (pinfunction "IO_28") (pintype "bidirectional"))
    )
    (net (code "94") (name "unconnected-(U4E-IO-Pad29)") (class "Default")
      (node (ref "U4") (pin "29") (pinfunction "IO_29") (pintype "bidirectional"))
    )
    (net (code "95") (name "unconnected-(U4E-IO-Pad30)") (class "Default")
      (node (ref "U4") (pin "30") (pinfunction "IO_30") (pintype "bidirectional"))
    )
    (net (code "96") (name "unconnected-(U4E-IO-Pad33)") (class "Default")
      (node (ref "U4") (pin "33") (pinfunction "IO_33") (pintype "bidirectional"))
    )
    (net (code "97") (name "unconnected-(U4E-IO-Pad34)") (class "Default")
      (node (ref "U4") (pin "34") (pinfunction "IO_34") (pintype "bidirectional"))
    )
    (net (code "98") (name "unconnected-(U4E-IODEV_CLRn-Pad44)") (class "Default")
      (node (ref "U4") (pin "44") (pinfunction "IODEV_CLRn_44") (pintype "bidirectional"))
    )
    (net (code "99") (name "unconnected-(U4E-IODEV_OE-Pad43)") (class "Default")
      (node (ref "U4") (pin "43") (pinfunction "IODEV_OE_43") (pintype "bidirectional"))
    )
    (net (code "100") (name "unconnected-(U4E-IOGCLK0-Pad12)") (class "Default")
      (node (ref "U4") (pin "12") (pinfunction "IOGCLK0_12") (pintype "bidirectional"))
    )
    (net (code "101") (name "unconnected-(U4E-IOGCLK1-Pad14)") (class "Default")
      (node (ref "U4") (pin "14") (pinfunction "IOGCLK1_14") (pintype "bidirectional"))
    )
  )
)
